# sinduino.net
KiCad netlist of a schematic drawn in EAGLE
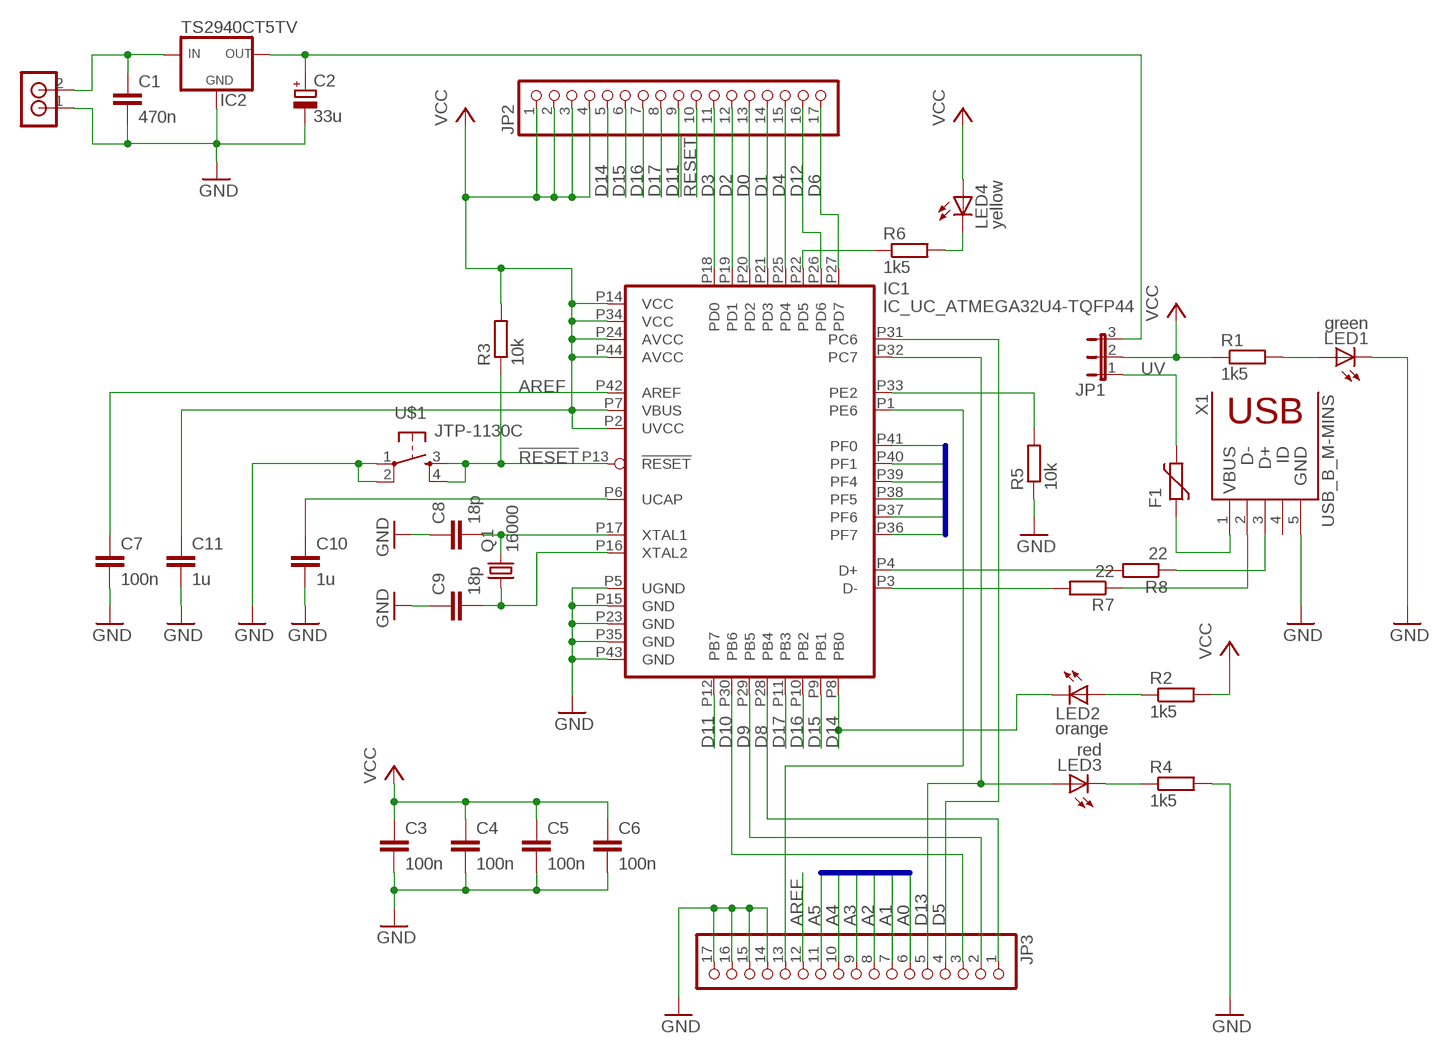
[diagram p0: schematic, sheet 1]

(export (version "E")
  (design (tool "Eeschema 10.0.6"))
  (components
    (comp (ref "C1")
      (value "470n")
      (footprint "eagle-import:C025-025X050")
      (libsource (lib "eagle-import") (part "C-EU025-025X050"))
    )
    (comp (ref "C2")
      (value "33u")
      (footprint "eagle-import:E2,5-5")
      (libsource (lib "eagle-import") (part "CPOL-EUE2.5-5"))
    )
    (comp (ref "C3")
      (value "100n")
      (footprint "eagle-import:C1206")
      (libsource (lib "eagle-import") (part "C-EUC1206"))
    )
    (comp (ref "C4")
      (value "100n")
      (footprint "eagle-import:C1206")
      (libsource (lib "eagle-import") (part "C-EUC1206"))
    )
    (comp (ref "C5")
      (value "100n")
      (footprint "eagle-import:C1206")
      (libsource (lib "eagle-import") (part "C-EUC1206"))
    )
    (comp (ref "C6")
      (value "100n")
      (footprint "eagle-import:C1206")
      (libsource (lib "eagle-import") (part "C-EUC1206"))
    )
    (comp (ref "C7")
      (value "100n")
      (footprint "eagle-import:C1206")
      (libsource (lib "eagle-import") (part "C-EUC1206"))
    )
    (comp (ref "C8")
      (value "18p")
      (footprint "eagle-import:C1206")
      (libsource (lib "eagle-import") (part "C-EUC1206"))
    )
    (comp (ref "C9")
      (value "18p")
      (footprint "eagle-import:C1206")
      (libsource (lib "eagle-import") (part "C-EUC1206"))
    )
    (comp (ref "C10")
      (value "1u")
      (footprint "eagle-import:C1206")
      (libsource (lib "eagle-import") (part "C-EUC1206"))
    )
    (comp (ref "C11")
      (value "1u")
      (footprint "eagle-import:C1206")
      (libsource (lib "eagle-import") (part "C-EUC1206"))
    )
    (comp (ref "F1")
      (value "FUSE_PTC-1812")
      (footprint "eagle-import:PTC1812L")
      (libsource (lib "eagle-import") (part "FUSE_PTC-1812"))
    )
    (comp (ref "IC1")
      (value "IC_UC_ATMEGA32U4-TQFP44")
      (footprint "eagle-import:TQFP-44")
      (libsource (lib "eagle-import") (part "IC_UC_ATMEGA32U4-TQFP44"))
    )
    (comp (ref "IC2")
      (value "TS2940CT5TV")
      (footprint "eagle-import:TO220V")
      (libsource (lib "eagle-import") (part "TS2940TVCT5"))
    )
    (comp (ref "JP1")
      (value "JP2E")
      (footprint "eagle-import:JP2")
      (libsource (lib "eagle-import") (part "JP2E"))
    )
    (comp (ref "JP2")
      (value "PINHD-1X17")
      (footprint "eagle-import:1X17")
      (libsource (lib "eagle-import") (part "PINHD-1X17"))
    )
    (comp (ref "JP3")
      (value "PINHD-1X17")
      (footprint "eagle-import:1X17")
      (libsource (lib "eagle-import") (part "PINHD-1X17"))
    )
    (comp (ref "LED1")
      (value "green")
      (footprint "eagle-import:LED3MM")
      (libsource (lib "eagle-import") (part "LED3MM"))
    )
    (comp (ref "LED2")
      (value "orange")
      (footprint "eagle-import:LED3MM")
      (libsource (lib "eagle-import") (part "LED3MM"))
    )
    (comp (ref "LED3")
      (value "red")
      (footprint "eagle-import:LED3MM")
      (libsource (lib "eagle-import") (part "LED3MM"))
    )
    (comp (ref "LED4")
      (value "yellow")
      (footprint "eagle-import:LED3MM")
      (libsource (lib "eagle-import") (part "LED3MM"))
    )
    (comp (ref "Q1")
      (value "16000")
      (footprint "eagle-import:HC49U-V")
      (libsource (lib "eagle-import") (part "CRYSTALHC49U-V"))
    )
    (comp (ref "R1")
      (value "1k5")
      (footprint "eagle-import:R1206")
      (libsource (lib "eagle-import") (part "R-EU_R1206"))
    )
    (comp (ref "R2")
      (value "1k5")
      (footprint "eagle-import:R1206")
      (libsource (lib "eagle-import") (part "R-EU_R1206"))
    )
    (comp (ref "R3")
      (value "10k")
      (footprint "eagle-import:R1206")
      (libsource (lib "eagle-import") (part "R-EU_R1206"))
    )
    (comp (ref "R4")
      (value "1k5")
      (footprint "eagle-import:R1206")
      (libsource (lib "eagle-import") (part "R-EU_R1206"))
    )
    (comp (ref "R5")
      (value "10k")
      (footprint "eagle-import:R1206")
      (libsource (lib "eagle-import") (part "R-EU_R1206"))
    )
    (comp (ref "R6")
      (value "1k5")
      (footprint "eagle-import:R1206")
      (libsource (lib "eagle-import") (part "R-EU_R1206"))
    )
    (comp (ref "R7")
      (value "22")
      (footprint "eagle-import:R1206")
      (libsource (lib "eagle-import") (part "R-EU_R1206"))
    )
    (comp (ref "R8")
      (value "22")
      (footprint "eagle-import:R1206")
      (libsource (lib "eagle-import") (part "R-EU_R1206"))
    )
    (comp (ref "U$1")
      (value "JTP-1130C")
      (footprint "eagle-import:JTP-1130")
      (libsource (lib "eagle-import") (part "JTP-1130C"))
    )
    (comp (ref "U$3")
      (value "RIACON_101_2")
      (footprint "eagle-import:RIACON_101_2")
      (libsource (lib "eagle-import") (part "RIACON_101_2"))
    )
    (comp (ref "X1")
      (value "USB_B_M-MINS")
      (footprint "eagle-import:LUMBERG_2486-01")
      (libsource (lib "eagle-import") (part "USB_B_M-MINS"))
    )
  )
  (nets
    (net (code "1") (name "/A0") (class "Default")
      (node (ref "IC1") (pin "P36") (pinfunction "PF7_P36") (pintype "bidirectional"))
      (node (ref "JP3") (pin "6") (pinfunction "6_6") (pintype "passive"))
    )
    (net (code "2") (name "/A1") (class "Default")
      (node (ref "IC1") (pin "P37") (pinfunction "PF6_P37") (pintype "bidirectional"))
      (node (ref "JP3") (pin "7") (pinfunction "7_7") (pintype "passive"))
    )
    (net (code "3") (name "/A2") (class "Default")
      (node (ref "IC1") (pin "P38") (pinfunction "PF5_P38") (pintype "bidirectional"))
      (node (ref "JP3") (pin "8") (pinfunction "8_8") (pintype "passive"))
    )
    (net (code "4") (name "/A3") (class "Default")
      (node (ref "IC1") (pin "P39") (pinfunction "PF4_P39") (pintype "bidirectional"))
      (node (ref "JP3") (pin "9") (pinfunction "9_9") (pintype "passive"))
    )
    (net (code "5") (name "/A4") (class "Default")
      (node (ref "IC1") (pin "P40") (pinfunction "PF1_P40") (pintype "bidirectional"))
      (node (ref "JP3") (pin "10") (pinfunction "10_10") (pintype "passive"))
    )
    (net (code "6") (name "/A5") (class "Default")
      (node (ref "IC1") (pin "P41") (pinfunction "PF0_P41") (pintype "bidirectional"))
      (node (ref "JP3") (pin "11") (pinfunction "11_11") (pintype "passive"))
    )
    (net (code "7") (name "/AREF") (class "Default")
      (node (ref "C7") (pin "1") (pinfunction "1_1") (pintype "passive"))
      (node (ref "IC1") (pin "P42") (pinfunction "AREF_P42") (pintype "power_in"))
      (node (ref "JP3") (pin "12") (pinfunction "12_12") (pintype "passive"))
    )
    (net (code "8") (name "/D0") (class "Default")
      (node (ref "IC1") (pin "P20") (pinfunction "PD2_P20") (pintype "bidirectional"))
      (node (ref "JP2") (pin "13") (pinfunction "13_13") (pintype "passive"))
    )
    (net (code "9") (name "/D1") (class "Default")
      (node (ref "IC1") (pin "P21") (pinfunction "PD3_P21") (pintype "bidirectional"))
      (node (ref "JP2") (pin "14") (pinfunction "14_14") (pintype "passive"))
    )
    (net (code "10") (name "/D2") (class "Default")
      (node (ref "IC1") (pin "P19") (pinfunction "PD1_P19") (pintype "bidirectional"))
      (node (ref "JP2") (pin "12") (pinfunction "12_12") (pintype "passive"))
    )
    (net (code "11") (name "/D3") (class "Default")
      (node (ref "IC1") (pin "P18") (pinfunction "PD0_P18") (pintype "bidirectional"))
      (node (ref "JP2") (pin "11") (pinfunction "11_11") (pintype "passive"))
    )
    (net (code "12") (name "/D4") (class "Default")
      (node (ref "IC1") (pin "P25") (pinfunction "PD4_P25") (pintype "bidirectional"))
      (node (ref "JP2") (pin "15") (pinfunction "15_15") (pintype "passive"))
    )
    (net (code "13") (name "/D5") (class "Default")
      (node (ref "IC1") (pin "P31") (pinfunction "PC6_P31") (pintype "bidirectional"))
      (node (ref "JP3") (pin "4") (pinfunction "4_4") (pintype "passive"))
    )
    (net (code "14") (name "/D6") (class "Default")
      (node (ref "IC1") (pin "P27") (pinfunction "PD7_P27") (pintype "bidirectional"))
      (node (ref "JP2") (pin "17") (pinfunction "17_17") (pintype "passive"))
    )
    (net (code "15") (name "/D8") (class "Default")
      (node (ref "IC1") (pin "P28") (pinfunction "PB4_P28") (pintype "bidirectional"))
      (node (ref "JP3") (pin "1") (pinfunction "1_1") (pintype "passive"))
    )
    (net (code "16") (name "/D9") (class "Default")
      (node (ref "IC1") (pin "P29") (pinfunction "PB5_P29") (pintype "bidirectional"))
      (node (ref "JP3") (pin "2") (pinfunction "2_2") (pintype "passive"))
    )
    (net (code "17") (name "/D10") (class "Default")
      (node (ref "IC1") (pin "P30") (pinfunction "PB6_P30") (pintype "bidirectional"))
      (node (ref "JP3") (pin "3") (pinfunction "3_3") (pintype "passive"))
    )
    (net (code "18") (name "/D11") (class "Default")
      (node (ref "IC1") (pin "P12") (pinfunction "PB7_P12") (pintype "bidirectional"))
      (node (ref "JP2") (pin "9") (pinfunction "9_9") (pintype "passive"))
    )
    (net (code "19") (name "/D12") (class "Default")
      (node (ref "IC1") (pin "P26") (pinfunction "PD6_P26") (pintype "bidirectional"))
      (node (ref "JP2") (pin "16") (pinfunction "16_16") (pintype "passive"))
    )
    (net (code "20") (name "/D13") (class "Default")
      (node (ref "IC1") (pin "P32") (pinfunction "PC7_P32") (pintype "bidirectional"))
      (node (ref "JP3") (pin "5") (pinfunction "5_5") (pintype "passive"))
      (node (ref "LED3") (pin "A") (pinfunction "A_A") (pintype "passive"))
    )
    (net (code "21") (name "/D14") (class "Default")
      (node (ref "IC1") (pin "P8") (pinfunction "PB0_P8") (pintype "bidirectional"))
      (node (ref "JP2") (pin "5") (pinfunction "5_5") (pintype "passive"))
      (node (ref "LED2") (pin "K") (pinfunction "C_K") (pintype "passive"))
    )
    (net (code "22") (name "/D15") (class "Default")
      (node (ref "IC1") (pin "P9") (pinfunction "PB1_P9") (pintype "bidirectional"))
      (node (ref "JP2") (pin "6") (pinfunction "6_6") (pintype "passive"))
    )
    (net (code "23") (name "/D16") (class "Default")
      (node (ref "IC1") (pin "P10") (pinfunction "PB2_P10") (pintype "bidirectional"))
      (node (ref "JP2") (pin "7") (pinfunction "7_7") (pintype "passive"))
    )
    (net (code "24") (name "/D17") (class "Default")
      (node (ref "IC1") (pin "P11") (pinfunction "PB3_P11") (pintype "bidirectional"))
      (node (ref "JP2") (pin "8") (pinfunction "8_8") (pintype "passive"))
    )
    (net (code "25") (name "/UV") (class "Default")
      (node (ref "F1") (pin "2") (pinfunction "2_2") (pintype "passive"))
      (node (ref "JP1") (pin "1") (pinfunction "1_1") (pintype "passive"))
    )
    (net (code "26") (name "/~{RESET}") (class "Default")
      (node (ref "IC1") (pin "P13") (pinfunction "~{RESET}_P13") (pintype "input"))
      (node (ref "JP2") (pin "10") (pinfunction "10_10") (pintype "passive"))
      (node (ref "R3") (pin "1") (pinfunction "1_1") (pintype "passive"))
      (node (ref "U$1") (pin "3") (pinfunction "S_3") (pintype "passive"))
      (node (ref "U$1") (pin "4") (pinfunction "S1_4") (pintype "passive"))
    )
    (net (code "27") (name "GND") (class "Default")
      (node (ref "C1") (pin "2") (pinfunction "2_2") (pintype "passive"))
      (node (ref "C10") (pin "2") (pinfunction "2_2") (pintype "passive"))
      (node (ref "C11") (pin "2") (pinfunction "2_2") (pintype "passive"))
      (node (ref "C2") (pin "-") (pinfunction "-_-") (pintype "passive"))
      (node (ref "C3") (pin "2") (pinfunction "2_2") (pintype "passive"))
      (node (ref "C4") (pin "2") (pinfunction "2_2") (pintype "passive"))
      (node (ref "C5") (pin "2") (pinfunction "2_2") (pintype "passive"))
      (node (ref "C6") (pin "2") (pinfunction "2_2") (pintype "passive"))
      (node (ref "C7") (pin "2") (pinfunction "2_2") (pintype "passive"))
      (node (ref "C8") (pin "1") (pinfunction "1_1") (pintype "passive"))
      (node (ref "C9") (pin "1") (pinfunction "1_1") (pintype "passive"))
      (node (ref "IC1") (pin "P15") (pinfunction "GND_P15") (pintype "power_in"))
      (node (ref "IC1") (pin "P23") (pinfunction "GND_P23") (pintype "power_in"))
      (node (ref "IC1") (pin "P35") (pinfunction "GND_P35") (pintype "power_in"))
      (node (ref "IC1") (pin "P43") (pinfunction "GND_P43") (pintype "power_in"))
      (node (ref "IC1") (pin "P5") (pinfunction "UGND_P5") (pintype "power_in"))
      (node (ref "IC2") (pin "2") (pinfunction "GND_2") (pintype "power_in"))
      (node (ref "JP3") (pin "14") (pinfunction "14_14") (pintype "passive"))
      (node (ref "JP3") (pin "15") (pinfunction "15_15") (pintype "passive"))
      (node (ref "JP3") (pin "16") (pinfunction "16_16") (pintype "passive"))
      (node (ref "JP3") (pin "17") (pinfunction "17_17") (pintype "passive"))
      (node (ref "LED1") (pin "K") (pinfunction "C_K") (pintype "passive"))
      (node (ref "R4") (pin "2") (pinfunction "2_2") (pintype "passive"))
      (node (ref "R5") (pin "1") (pinfunction "1_1") (pintype "passive"))
      (node (ref "U$1") (pin "1") (pinfunction "P_1") (pintype "passive"))
      (node (ref "U$1") (pin "2") (pinfunction "P1_2") (pintype "passive"))
      (node (ref "U$3") (pin "1") (pinfunction "1_1") (pintype "passive"))
      (node (ref "X1") (pin "5") (pinfunction "5_5") (pintype "passive"))
    )
    (net (code "28") (name "Net-(F1-Pad1)") (class "Default")
      (node (ref "F1") (pin "1") (pinfunction "1_1") (pintype "passive"))
      (node (ref "X1") (pin "1") (pinfunction "1_1") (pintype "passive"))
    )
    (net (code "29") (name "Net-(IC1-D+)") (class "Default")
      (node (ref "IC1") (pin "P4") (pinfunction "D+_P4") (pintype "bidirectional"))
      (node (ref "R8") (pin "2") (pinfunction "2_2") (pintype "passive"))
    )
    (net (code "30") (name "Net-(IC1-D-)") (class "Default")
      (node (ref "IC1") (pin "P3") (pinfunction "D-_P3") (pintype "bidirectional"))
      (node (ref "R7") (pin "2") (pinfunction "2_2") (pintype "passive"))
    )
    (net (code "31") (name "Net-(IC1-PD5)") (class "Default")
      (node (ref "IC1") (pin "P22") (pinfunction "PD5_P22") (pintype "bidirectional"))
      (node (ref "R6") (pin "1") (pinfunction "1_1") (pintype "passive"))
    )
    (net (code "32") (name "Net-(IC1-PE2)") (class "Default")
      (node (ref "IC1") (pin "P33") (pinfunction "PE2_P33") (pintype "bidirectional"))
      (node (ref "R5") (pin "2") (pinfunction "2_2") (pintype "passive"))
    )
    (net (code "33") (name "Net-(IC1-PE6)") (class "Default")
      (node (ref "IC1") (pin "P1") (pinfunction "PE6_P1") (pintype "bidirectional"))
      (node (ref "JP3") (pin "13") (pinfunction "13_13") (pintype "passive"))
    )
    (net (code "34") (name "Net-(IC1-UCAP)") (class "Default")
      (node (ref "C10") (pin "1") (pinfunction "1_1") (pintype "passive"))
      (node (ref "IC1") (pin "P6") (pinfunction "UCAP_P6") (pintype "power_in"))
    )
    (net (code "35") (name "Net-(IC1-XTAL1)") (class "Default")
      (node (ref "C8") (pin "2") (pinfunction "2_2") (pintype "passive"))
      (node (ref "IC1") (pin "P17") (pinfunction "XTAL1_P17") (pintype "bidirectional"))
      (node (ref "Q1") (pin "2") (pinfunction "2_2") (pintype "passive"))
    )
    (net (code "36") (name "Net-(IC1-XTAL2)") (class "Default")
      (node (ref "C9") (pin "2") (pinfunction "2_2") (pintype "passive"))
      (node (ref "IC1") (pin "P16") (pinfunction "XTAL2_P16") (pintype "bidirectional"))
      (node (ref "Q1") (pin "1") (pinfunction "1_1") (pintype "passive"))
    )
    (net (code "37") (name "Net-(IC2-IN)") (class "Default")
      (node (ref "C1") (pin "1") (pinfunction "1_1") (pintype "passive"))
      (node (ref "IC2") (pin "1") (pinfunction "IN_1") (pintype "power_in"))
      (node (ref "U$3") (pin "2") (pinfunction "2_2") (pintype "passive"))
    )
    (net (code "38") (name "Net-(IC2-OUT)") (class "Default")
      (node (ref "C2") (pin "+") (pinfunction "+_+") (pintype "passive"))
      (node (ref "IC2") (pin "3") (pinfunction "OUT_3") (pintype "power_in"))
      (node (ref "JP1") (pin "3") (pinfunction "3_3") (pintype "passive"))
    )
    (net (code "39") (name "Net-(LED1-PadA)") (class "Default")
      (node (ref "LED1") (pin "A") (pinfunction "A_A") (pintype "passive"))
      (node (ref "R1") (pin "2") (pinfunction "2_2") (pintype "passive"))
    )
    (net (code "40") (name "Net-(LED2-PadA)") (class "Default")
      (node (ref "LED2") (pin "A") (pinfunction "A_A") (pintype "passive"))
      (node (ref "R2") (pin "1") (pinfunction "1_1") (pintype "passive"))
    )
    (net (code "41") (name "Net-(LED3-C)") (class "Default")
      (node (ref "LED3") (pin "K") (pinfunction "C_K") (pintype "passive"))
      (node (ref "R4") (pin "1") (pinfunction "1_1") (pintype "passive"))
    )
    (net (code "42") (name "Net-(LED4-C)") (class "Default")
      (node (ref "LED4") (pin "K") (pinfunction "C_K") (pintype "passive"))
      (node (ref "R6") (pin "2") (pinfunction "2_2") (pintype "passive"))
    )
    (net (code "43") (name "Net-(R7-Pad1)") (class "Default")
      (node (ref "R7") (pin "1") (pinfunction "1_1") (pintype "passive"))
      (node (ref "X1") (pin "2") (pinfunction "2_2") (pintype "passive"))
    )
    (net (code "44") (name "Net-(R8-Pad1)") (class "Default")
      (node (ref "R8") (pin "1") (pinfunction "1_1") (pintype "passive"))
      (node (ref "X1") (pin "3") (pinfunction "3_3") (pintype "passive"))
    )
    (net (code "45") (name "VCC") (class "Default")
      (node (ref "C11") (pin "1") (pinfunction "1_1") (pintype "passive"))
      (node (ref "C3") (pin "1") (pinfunction "1_1") (pintype "passive"))
      (node (ref "C4") (pin "1") (pinfunction "1_1") (pintype "passive"))
      (node (ref "C5") (pin "1") (pinfunction "1_1") (pintype "passive"))
      (node (ref "C6") (pin "1") (pinfunction "1_1") (pintype "passive"))
      (node (ref "IC1") (pin "P14") (pinfunction "VCC_P14") (pintype "power_in"))
      (node (ref "IC1") (pin "P2") (pinfunction "UVCC_P2") (pintype "power_in"))
      (node (ref "IC1") (pin "P24") (pinfunction "AVCC_P24") (pintype "power_in"))
      (node (ref "IC1") (pin "P34") (pinfunction "VCC_P34") (pintype "power_in"))
      (node (ref "IC1") (pin "P44") (pinfunction "AVCC_P44") (pintype "power_in"))
      (node (ref "IC1") (pin "P7") (pinfunction "VBUS_P7") (pintype "power_in"))
      (node (ref "JP1") (pin "2") (pinfunction "2_2") (pintype "passive"))
      (node (ref "JP2") (pin "1") (pinfunction "1_1") (pintype "passive"))
      (node (ref "JP2") (pin "2") (pinfunction "2_2") (pintype "passive"))
      (node (ref "JP2") (pin "3") (pinfunction "3_3") (pintype "passive"))
      (node (ref "JP2") (pin "4") (pinfunction "4_4") (pintype "passive"))
      (node (ref "LED4") (pin "A") (pinfunction "A_A") (pintype "passive"))
      (node (ref "R1") (pin "1") (pinfunction "1_1") (pintype "passive"))
      (node (ref "R2") (pin "2") (pinfunction "2_2") (pintype "passive"))
      (node (ref "R3") (pin "2") (pinfunction "2_2") (pintype "passive"))
    )
    (net (code "46") (name "unconnected-(X1-Pad4)") (class "Default")
      (node (ref "X1") (pin "4") (pinfunction "4_4") (pintype "passive"))
    )
  )
)
